# Fastino_Supply_Switching.net
KiCad netlist of a schematic drawn in Altium Designer
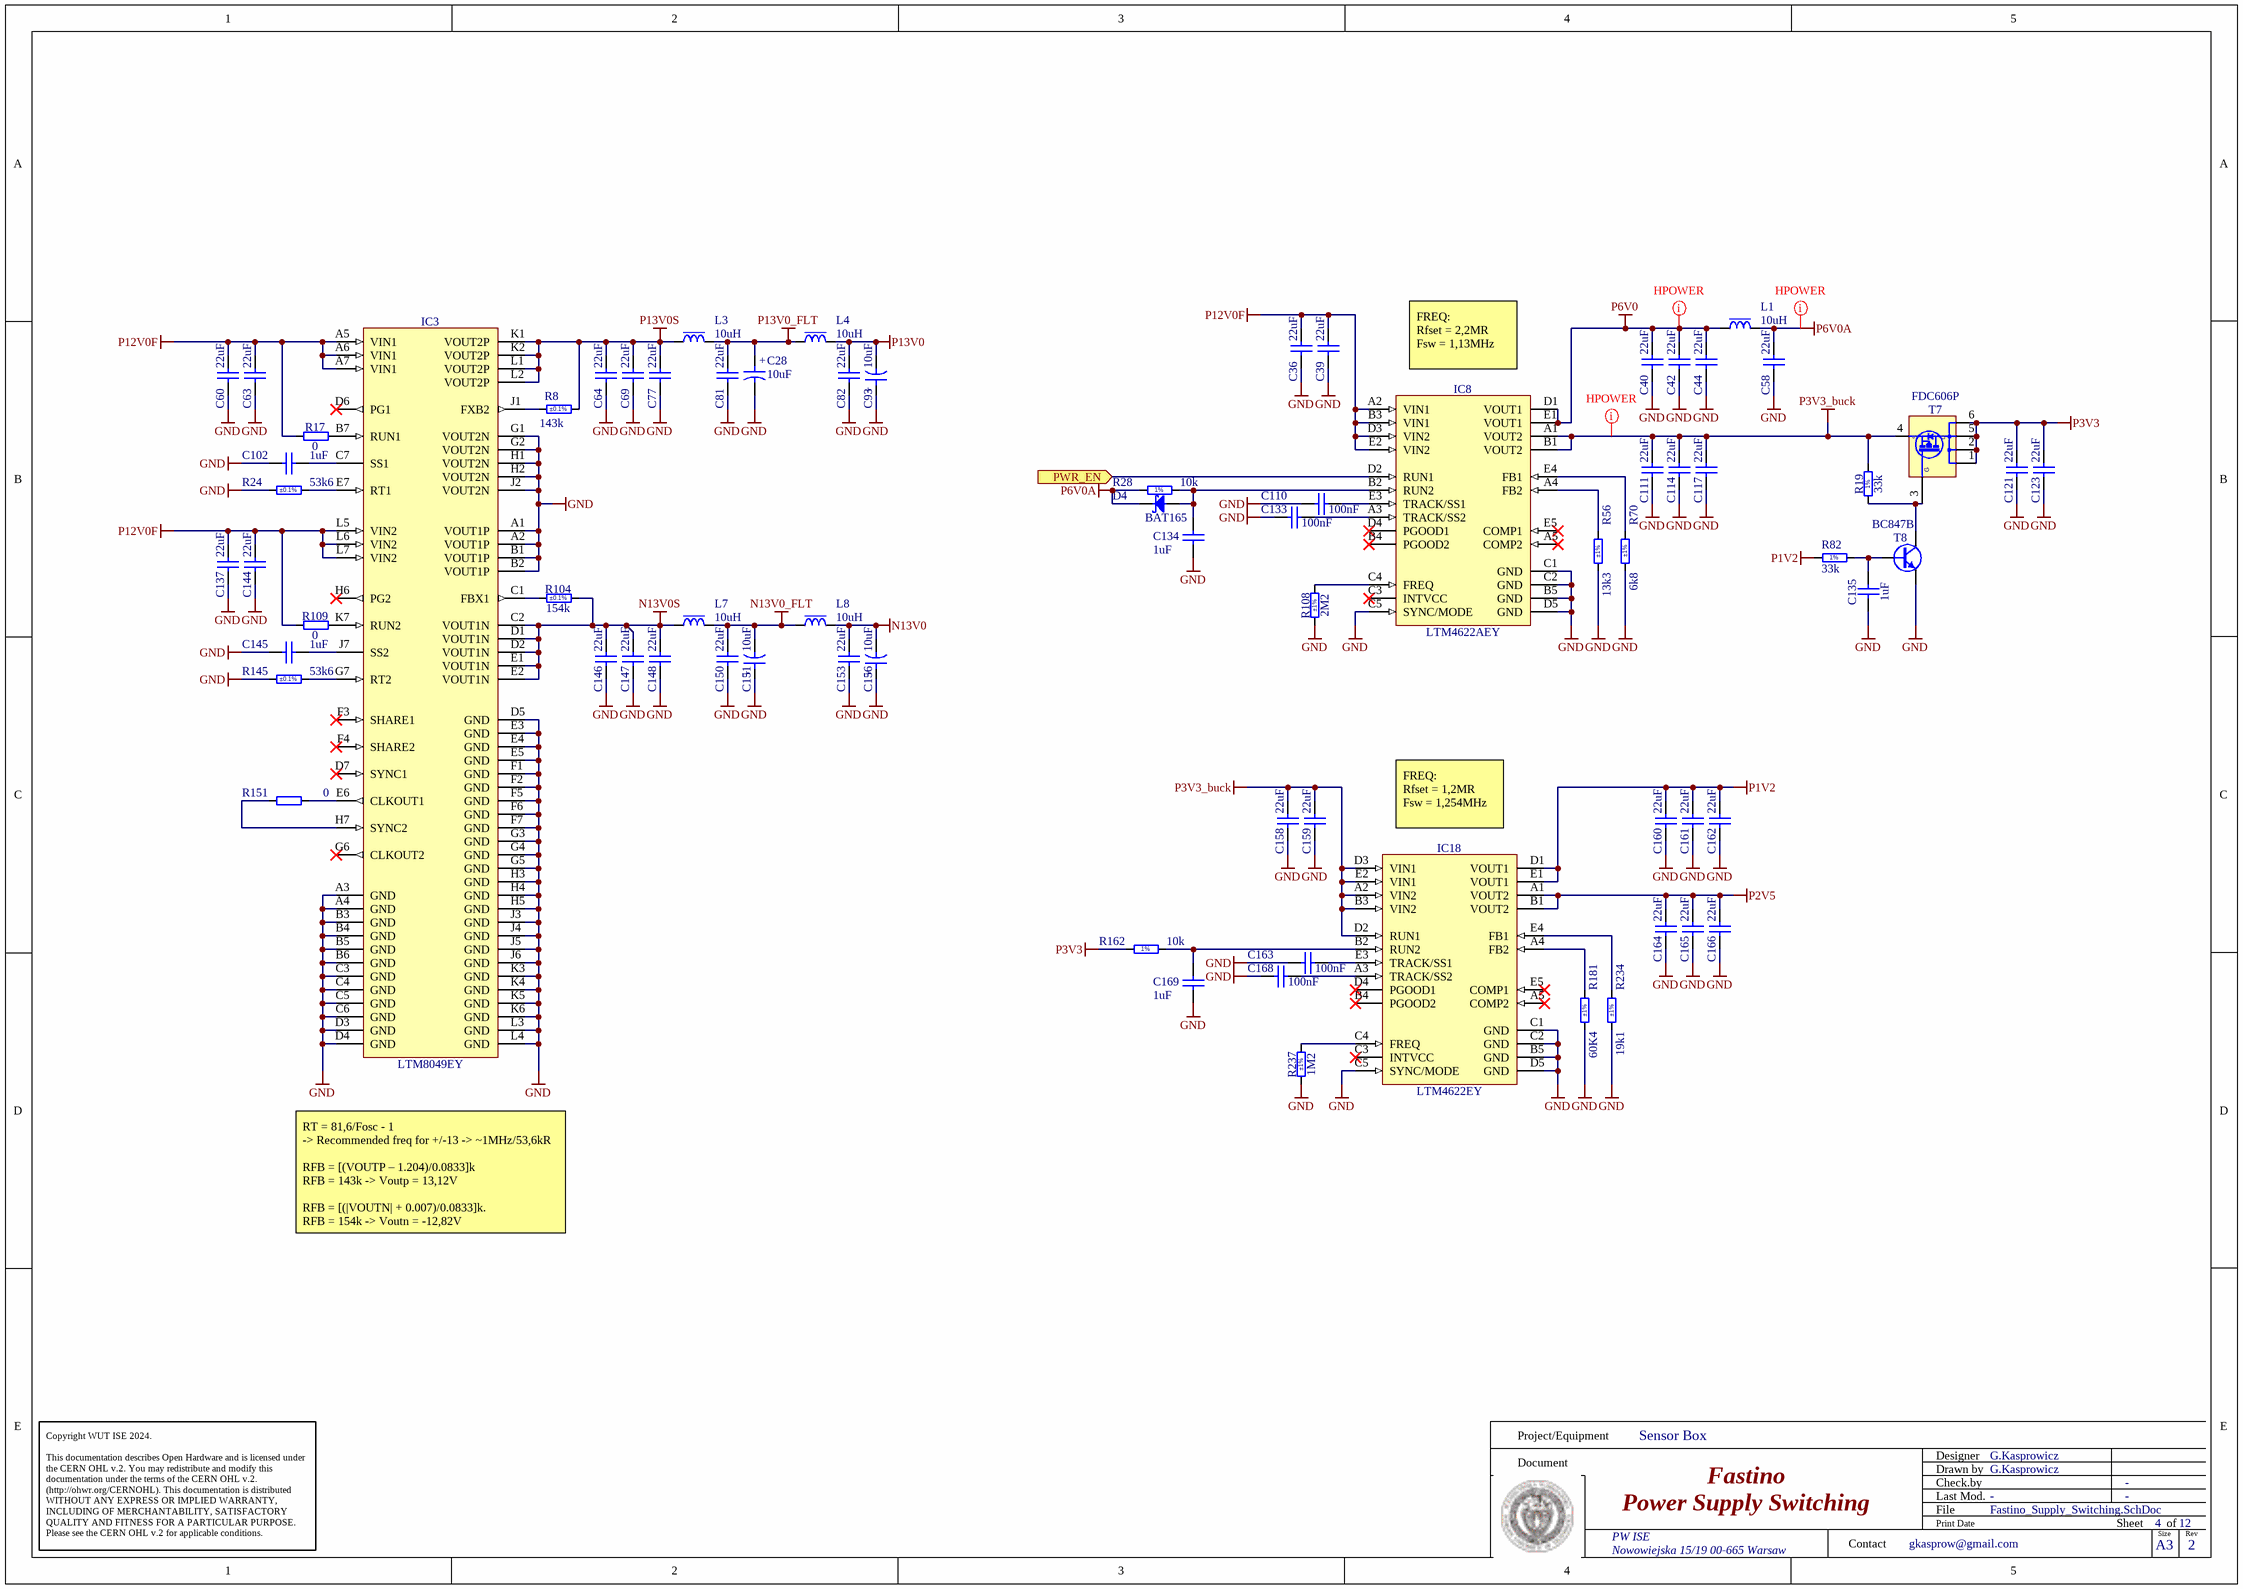
[diagram p0: Fastino_Supply_Switching.SchDoc]

(export (version "E")
  (design (tool "Eeschema 10.0.6"))
  (components
    (comp (ref "C28")
      (value "10uF")
      (footprint "CAPMP3216X180N")
      (description "Polarised capacitor")
      (fields
        (field (name "PART NUMBER") "CTE3216-18_10UF_16V_20%_AVX_TCJ")
        (field (name "VOLTAGE") "16V")
        (field (name "AUTHOR") "CERN DEM JLC")
      )
      (libsource (lib "Capacitors") (part "Capacitor - polarized"))
    )
    (comp (ref "C36")
      (value "22uF")
      (footprint "CAPC2012X135N")
      (description "Non-polarised capacitor")
      (fields
        (field (name "PART NUMBER") "CC0805_22UF_16V_10%_X5R")
        (field (name "VOLTAGE") "16V")
        (field (name "AUTHOR") "CERN DEM JLC")
      )
      (libsource (lib "Capacitors") (part "Capacitor - non polarized"))
    )
    (comp (ref "C39")
      (value "22uF")
      (footprint "CAPC2012X135N")
      (description "Non-polarised capacitor")
      (fields
        (field (name "PART NUMBER") "CC0805_22UF_16V_10%_X5R")
        (field (name "VOLTAGE") "16V")
        (field (name "AUTHOR") "CERN DEM JLC")
      )
      (libsource (lib "Capacitors") (part "Capacitor - non polarized"))
    )
    (comp (ref "C40")
      (value "22uF")
      (footprint "CAPC2012X135N")
      (description "Non-polarised capacitor")
      (fields
        (field (name "PART NUMBER") "CC0805_22UF_16V_10%_X5R")
        (field (name "VOLTAGE") "16V")
        (field (name "AUTHOR") "CERN DEM JLC")
      )
      (libsource (lib "Capacitors") (part "Capacitor - non polarized"))
    )
    (comp (ref "C42")
      (value "22uF")
      (footprint "CAPC2012X135N")
      (description "Non-polarised capacitor")
      (fields
        (field (name "PART NUMBER") "CC0805_22UF_16V_10%_X5R")
        (field (name "VOLTAGE") "16V")
        (field (name "AUTHOR") "CERN DEM JLC")
      )
      (libsource (lib "Capacitors") (part "Capacitor - non polarized"))
    )
    (comp (ref "C44")
      (value "22uF")
      (footprint "CAPC2012X135N")
      (description "Non-polarised capacitor")
      (fields
        (field (name "PART NUMBER") "CC0805_22UF_16V_10%_X5R")
        (field (name "VOLTAGE") "16V")
        (field (name "AUTHOR") "CERN DEM JLC")
      )
      (libsource (lib "Capacitors") (part "Capacitor - non polarized"))
    )
    (comp (ref "C58")
      (value "22uF")
      (footprint "CAPC2012X135N")
      (description "Non-polarised capacitor")
      (fields
        (field (name "PART NUMBER") "CC0805_22UF_16V_10%_X5R")
        (field (name "VOLTAGE") "16V")
        (field (name "AUTHOR") "CERN DEM JLC")
      )
      (libsource (lib "Capacitors") (part "Capacitor - non polarized"))
    )
    (comp (ref "C60")
      (value "22uF")
      (footprint "CAPC2012X135N")
      (description "Non-polarised capacitor")
      (fields
        (field (name "PART NUMBER") "CC0805_22UF_16V_10%_X5R")
        (field (name "VOLTAGE") "16V")
        (field (name "AUTHOR") "CERN DEM JLC")
      )
      (libsource (lib "Capacitors") (part "Capacitor - non polarized"))
    )
    (comp (ref "C63")
      (value "22uF")
      (footprint "CAPC2012X135N")
      (description "Non-polarised capacitor")
      (fields
        (field (name "PART NUMBER") "CC0805_22UF_16V_10%_X5R")
        (field (name "VOLTAGE") "16V")
        (field (name "AUTHOR") "CERN DEM JLC")
      )
      (libsource (lib "Capacitors") (part "Capacitor - non polarized"))
    )
    (comp (ref "C64")
      (value "22uF")
      (footprint "CAPC2012X135N")
      (description "Non-polarised capacitor")
      (fields
        (field (name "PART NUMBER") "CC0805_22UF_16V_10%_X5R")
        (field (name "VOLTAGE") "16V")
        (field (name "AUTHOR") "CERN DEM JLC")
      )
      (libsource (lib "Capacitors") (part "Capacitor - non polarized"))
    )
    (comp (ref "C69")
      (value "22uF")
      (footprint "CAPC2012X135N")
      (description "Non-polarised capacitor")
      (fields
        (field (name "PART NUMBER") "CC0805_22UF_16V_10%_X5R")
        (field (name "VOLTAGE") "16V")
        (field (name "AUTHOR") "CERN DEM JLC")
      )
      (libsource (lib "Capacitors") (part "Capacitor - non polarized"))
    )
    (comp (ref "C77")
      (value "22uF")
      (footprint "CAPC2012X135N")
      (description "Non-polarised capacitor")
      (fields
        (field (name "PART NUMBER") "CC0805_22UF_16V_10%_X5R")
        (field (name "VOLTAGE") "16V")
        (field (name "AUTHOR") "CERN DEM JLC")
      )
      (libsource (lib "Capacitors") (part "Capacitor - non polarized"))
    )
    (comp (ref "C81")
      (value "22uF")
      (footprint "CAPC2012X135N")
      (description "Non-polarised capacitor")
      (fields
        (field (name "PART NUMBER") "CC0805_22UF_16V_10%_X5R")
        (field (name "VOLTAGE") "16V")
        (field (name "AUTHOR") "CERN DEM JLC")
      )
      (libsource (lib "Capacitors") (part "Capacitor - non polarized"))
    )
    (comp (ref "C82")
      (value "22uF")
      (footprint "CAPC2012X135N")
      (description "Non-polarised capacitor")
      (fields
        (field (name "PART NUMBER") "CC0805_22UF_16V_10%_X5R")
        (field (name "VOLTAGE") "16V")
        (field (name "AUTHOR") "CERN DEM JLC")
      )
      (libsource (lib "Capacitors") (part "Capacitor - non polarized"))
    )
    (comp (ref "C93")
      (value "10uF")
      (footprint "CAPMP3216X180N")
      (description "Polarised capacitor")
      (fields
        (field (name "PART NUMBER") "CTE3216-18_10UF_16V_20%_AVX_TCJ")
        (field (name "VOLTAGE") "16V")
        (field (name "AUTHOR") "CERN DEM JLC")
      )
      (libsource (lib "Capacitors") (part "Capacitor - polarized"))
    )
    (comp (ref "C102")
      (value "1uF")
      (footprint "CAPC1608X87N")
      (description "Non-polarised capacitor")
      (fields
        (field (name "PART NUMBER") "CC0603_1UF_25V_10%_X7R")
        (field (name "VOLTAGE") "25V")
        (field (name "AUTHOR") "CERN DEM JLC")
      )
      (libsource (lib "Capacitors") (part "Capacitor - non polarized"))
    )
    (comp (ref "C110")
      (value "100nF")
      (footprint "CAPC1005X55N")
      (description "Non-polarised capacitor")
      (fields
        (field (name "PART NUMBER") "CC0402_100NF_16V_10%_X5R")
        (field (name "VOLTAGE") "16V")
        (field (name "AUTHOR") "CERN DEM JLC")
      )
      (libsource (lib "Capacitors") (part "Capacitor - non polarized"))
    )
    (comp (ref "C111")
      (value "22uF")
      (footprint "CAPC2012X135N")
      (description "Non-polarised capacitor")
      (fields
        (field (name "PART NUMBER") "CC0805_22UF_16V_10%_X5R")
        (field (name "VOLTAGE") "16V")
        (field (name "AUTHOR") "CERN DEM JLC")
      )
      (libsource (lib "Capacitors") (part "Capacitor - non polarized"))
    )
    (comp (ref "C114")
      (value "22uF")
      (footprint "CAPC2012X135N")
      (description "Non-polarised capacitor")
      (fields
        (field (name "PART NUMBER") "CC0805_22UF_16V_10%_X5R")
        (field (name "VOLTAGE") "16V")
        (field (name "AUTHOR") "CERN DEM JLC")
      )
      (libsource (lib "Capacitors") (part "Capacitor - non polarized"))
    )
    (comp (ref "C117")
      (value "22uF")
      (footprint "CAPC2012X135N")
      (description "Non-polarised capacitor")
      (fields
        (field (name "PART NUMBER") "CC0805_22UF_16V_10%_X5R")
        (field (name "VOLTAGE") "16V")
        (field (name "AUTHOR") "CERN DEM JLC")
      )
      (libsource (lib "Capacitors") (part "Capacitor - non polarized"))
    )
    (comp (ref "C121")
      (value "22uF")
      (footprint "CAPC2012X135N")
      (description "Non-polarised capacitor")
      (fields
        (field (name "PART NUMBER") "CC0805_22UF_16V_10%_X5R")
        (field (name "VOLTAGE") "16V")
        (field (name "AUTHOR") "CERN DEM JLC")
      )
      (libsource (lib "Capacitors") (part "Capacitor - non polarized"))
    )
    (comp (ref "C123")
      (value "22uF")
      (footprint "CAPC2012X135N")
      (description "Non-polarised capacitor")
      (fields
        (field (name "PART NUMBER") "CC0805_22UF_16V_10%_X5R")
        (field (name "VOLTAGE") "16V")
        (field (name "AUTHOR") "CERN DEM JLC")
      )
      (libsource (lib "Capacitors") (part "Capacitor - non polarized"))
    )
    (comp (ref "C133")
      (value "100nF")
      (footprint "CAPC1005X55N")
      (description "Non-polarised capacitor")
      (fields
        (field (name "PART NUMBER") "CC0402_100NF_16V_10%_X5R")
        (field (name "VOLTAGE") "16V")
        (field (name "AUTHOR") "CERN DEM JLC")
      )
      (libsource (lib "Capacitors") (part "Capacitor - non polarized"))
    )
    (comp (ref "C134")
      (value "1uF")
      (footprint "CAPC1608X87N")
      (description "Non-polarised capacitor")
      (fields
        (field (name "PART NUMBER") "CC0603_1UF_25V_10%_X7R")
        (field (name "VOLTAGE") "25V")
        (field (name "AUTHOR") "CERN DEM JLC")
      )
      (libsource (lib "Capacitors") (part "Capacitor - non polarized"))
    )
    (comp (ref "C135")
      (value "1uF")
      (footprint "CAPC1608X87N")
      (description "Non-polarised capacitor")
      (fields
        (field (name "PART NUMBER") "CC0603_1UF_25V_10%_X7R")
        (field (name "VOLTAGE") "25V")
        (field (name "AUTHOR") "CERN DEM JLC")
      )
      (libsource (lib "Capacitors") (part "Capacitor - non polarized"))
    )
    (comp (ref "C137")
      (value "22uF")
      (footprint "CAPC2012X135N")
      (description "Non-polarised capacitor")
      (fields
        (field (name "PART NUMBER") "CC0805_22UF_16V_10%_X5R")
        (field (name "VOLTAGE") "16V")
        (field (name "AUTHOR") "CERN DEM JLC")
      )
      (libsource (lib "Capacitors") (part "Capacitor - non polarized"))
    )
    (comp (ref "C144")
      (value "22uF")
      (footprint "CAPC2012X135N")
      (description "Non-polarised capacitor")
      (fields
        (field (name "PART NUMBER") "CC0805_22UF_16V_10%_X5R")
        (field (name "VOLTAGE") "16V")
        (field (name "AUTHOR") "CERN DEM JLC")
      )
      (libsource (lib "Capacitors") (part "Capacitor - non polarized"))
    )
    (comp (ref "C145")
      (value "1uF")
      (footprint "CAPC1608X87N")
      (description "Non-polarised capacitor")
      (fields
        (field (name "PART NUMBER") "CC0603_1UF_25V_10%_X7R")
        (field (name "VOLTAGE") "25V")
        (field (name "AUTHOR") "CERN DEM JLC")
      )
      (libsource (lib "Capacitors") (part "Capacitor - non polarized"))
    )
    (comp (ref "C146")
      (value "22uF")
      (footprint "CAPC2012X135N")
      (description "Non-polarised capacitor")
      (fields
        (field (name "PART NUMBER") "CC0805_22UF_16V_10%_X5R")
        (field (name "VOLTAGE") "16V")
        (field (name "AUTHOR") "CERN DEM JLC")
      )
      (libsource (lib "Capacitors") (part "Capacitor - non polarized"))
    )
    (comp (ref "C147")
      (value "22uF")
      (footprint "CAPC2012X135N")
      (description "Non-polarised capacitor")
      (fields
        (field (name "PART NUMBER") "CC0805_22UF_16V_10%_X5R")
        (field (name "VOLTAGE") "16V")
        (field (name "AUTHOR") "CERN DEM JLC")
      )
      (libsource (lib "Capacitors") (part "Capacitor - non polarized"))
    )
    (comp (ref "C148")
      (value "22uF")
      (footprint "CAPC2012X135N")
      (description "Non-polarised capacitor")
      (fields
        (field (name "PART NUMBER") "CC0805_22UF_16V_10%_X5R")
        (field (name "VOLTAGE") "16V")
        (field (name "AUTHOR") "CERN DEM JLC")
      )
      (libsource (lib "Capacitors") (part "Capacitor - non polarized"))
    )
    (comp (ref "C150")
      (value "22uF")
      (footprint "CAPC2012X135N")
      (description "Non-polarised capacitor")
      (fields
        (field (name "PART NUMBER") "CC0805_22UF_16V_10%_X5R")
        (field (name "VOLTAGE") "16V")
        (field (name "AUTHOR") "CERN DEM JLC")
      )
      (libsource (lib "Capacitors") (part "Capacitor - non polarized"))
    )
    (comp (ref "C151")
      (value "10uF")
      (footprint "CAPMP3216X180N")
      (description "Polarised capacitor")
      (fields
        (field (name "PART NUMBER") "CTE3216-18_10UF_16V_20%_AVX_TCJ")
        (field (name "VOLTAGE") "16V")
        (field (name "AUTHOR") "CERN DEM JLC")
      )
      (libsource (lib "Capacitors") (part "Capacitor - polarized"))
    )
    (comp (ref "C153")
      (value "22uF")
      (footprint "CAPC2012X135N")
      (description "Non-polarised capacitor")
      (fields
        (field (name "PART NUMBER") "CC0805_22UF_16V_10%_X5R")
        (field (name "VOLTAGE") "16V")
        (field (name "AUTHOR") "CERN DEM JLC")
      )
      (libsource (lib "Capacitors") (part "Capacitor - non polarized"))
    )
    (comp (ref "C156")
      (value "10uF")
      (footprint "CAPMP3216X180N")
      (description "Polarised capacitor")
      (fields
        (field (name "PART NUMBER") "CTE3216-18_10UF_16V_20%_AVX_TCJ")
        (field (name "VOLTAGE") "16V")
        (field (name "AUTHOR") "CERN DEM JLC")
      )
      (libsource (lib "Capacitors") (part "Capacitor - polarized"))
    )
    (comp (ref "C158")
      (value "22uF")
      (footprint "CAPC2012X135N")
      (description "Non-polarised capacitor")
      (fields
        (field (name "PART NUMBER") "CC0805_22UF_16V_10%_X5R")
        (field (name "VOLTAGE") "16V")
        (field (name "AUTHOR") "CERN DEM JLC")
      )
      (libsource (lib "Capacitors") (part "Capacitor - non polarized"))
    )
    (comp (ref "C159")
      (value "22uF")
      (footprint "CAPC2012X135N")
      (description "Non-polarised capacitor")
      (fields
        (field (name "PART NUMBER") "CC0805_22UF_16V_10%_X5R")
        (field (name "VOLTAGE") "16V")
        (field (name "AUTHOR") "CERN DEM JLC")
      )
      (libsource (lib "Capacitors") (part "Capacitor - non polarized"))
    )
    (comp (ref "C160")
      (value "22uF")
      (footprint "CAPC2012X135N")
      (description "Non-polarised capacitor")
      (fields
        (field (name "PART NUMBER") "CC0805_22UF_16V_10%_X5R")
        (field (name "VOLTAGE") "16V")
        (field (name "AUTHOR") "CERN DEM JLC")
      )
      (libsource (lib "Capacitors") (part "Capacitor - non polarized"))
    )
    (comp (ref "C161")
      (value "22uF")
      (footprint "CAPC2012X135N")
      (description "Non-polarised capacitor")
      (fields
        (field (name "PART NUMBER") "CC0805_22UF_16V_10%_X5R")
        (field (name "VOLTAGE") "16V")
        (field (name "AUTHOR") "CERN DEM JLC")
      )
      (libsource (lib "Capacitors") (part "Capacitor - non polarized"))
    )
    (comp (ref "C162")
      (value "22uF")
      (footprint "CAPC2012X135N")
      (description "Non-polarised capacitor")
      (fields
        (field (name "PART NUMBER") "CC0805_22UF_16V_10%_X5R")
        (field (name "VOLTAGE") "16V")
        (field (name "AUTHOR") "CERN DEM JLC")
      )
      (libsource (lib "Capacitors") (part "Capacitor - non polarized"))
    )
    (comp (ref "C163")
      (value "100nF")
      (footprint "CAPC1005X55N")
      (description "Non-polarised capacitor")
      (fields
        (field (name "PART NUMBER") "CC0402_100NF_16V_10%_X5R")
        (field (name "VOLTAGE") "16V")
        (field (name "AUTHOR") "CERN DEM JLC")
      )
      (libsource (lib "Capacitors") (part "Capacitor - non polarized"))
    )
    (comp (ref "C164")
      (value "22uF")
      (footprint "CAPC2012X135N")
      (description "Non-polarised capacitor")
      (fields
        (field (name "PART NUMBER") "CC0805_22UF_16V_10%_X5R")
        (field (name "VOLTAGE") "16V")
        (field (name "AUTHOR") "CERN DEM JLC")
      )
      (libsource (lib "Capacitors") (part "Capacitor - non polarized"))
    )
    (comp (ref "C165")
      (value "22uF")
      (footprint "CAPC2012X135N")
      (description "Non-polarised capacitor")
      (fields
        (field (name "PART NUMBER") "CC0805_22UF_16V_10%_X5R")
        (field (name "VOLTAGE") "16V")
        (field (name "AUTHOR") "CERN DEM JLC")
      )
      (libsource (lib "Capacitors") (part "Capacitor - non polarized"))
    )
    (comp (ref "C166")
      (value "22uF")
      (footprint "CAPC2012X135N")
      (description "Non-polarised capacitor")
      (fields
        (field (name "PART NUMBER") "CC0805_22UF_16V_10%_X5R")
        (field (name "VOLTAGE") "16V")
        (field (name "AUTHOR") "CERN DEM JLC")
      )
      (libsource (lib "Capacitors") (part "Capacitor - non polarized"))
    )
    (comp (ref "C168")
      (value "100nF")
      (footprint "CAPC1005X55N")
      (description "Non-polarised capacitor")
      (fields
        (field (name "PART NUMBER") "CC0402_100NF_16V_10%_X5R")
        (field (name "VOLTAGE") "16V")
        (field (name "AUTHOR") "CERN DEM JLC")
      )
      (libsource (lib "Capacitors") (part "Capacitor - non polarized"))
    )
    (comp (ref "C169")
      (value "1uF")
      (footprint "CAPC1608X87N")
      (description "Non-polarised capacitor")
      (fields
        (field (name "PART NUMBER") "CC0603_1UF_25V_10%_X7R")
        (field (name "VOLTAGE") "25V")
        (field (name "AUTHOR") "CERN DEM JLC")
      )
      (libsource (lib "Capacitors") (part "Capacitor - non polarized"))
    )
    (comp (ref "D4")
      (value "BAT165")
      (footprint "SOD2512X110N")
      (description "Schottky Diode")
      (fields
        (field (name "MANUFACTURER") "INFINEON")
        (field (name "VOLTAGE") "40V")
        (field (name "AUTHOR") "CERN DEM JLC")
      )
      (libsource (lib "ICs And Semiconductors") (part "Diode Schottky"))
    )
    (comp (ref "IC3")
      (value "LTM8049EY")
      (footprint "BGA77C127P7X11_900X1500X262")
      (description "Dual SEPIC or Inverting uModule DC/DC Converter")
      (fields
        (field (name "PART NUMBER") "LTM8049EY#PBF")
        (field (name "MANUFACTURER") "LINEAR TECHNOLOGY")
        (field (name "AUTHOR") "CERN DEM JLC")
      )
      (libsource (lib "ICs And Semiconductors") (part "LTM8049"))
    )
    (comp (ref "IC8")
      (value "LTM4622AEY")
      (footprint "BGA25C127P5X5_625X625X262")
      (description "3.6V-20V To 1.5V-12V, Dual 2A or Single 4A  Ultrathin Step-Down DC/DC µModule Regulator")
      (fields
        (field (name "PART NUMBER") "LTM4622AEY#PBF")
        (field (name "MANUFACTURER") "LINEAR TECHNOLOGY")
        (field (name "AUTHOR") "CERN DEM MR")
      )
      (libsource (lib "ICs And Semiconductors") (part "LTM4622A"))
    )
    (comp (ref "IC18")
      (value "LTM4622EY")
      (footprint "BGA25C127P5X5_625X625X262")
      (description "3.6V-20V To 1.5V-12V, Dual 2A or Single 5A  Ultrathin Step-Down DC/DC µModule Regulator")
      (fields (field (name "MANUFACTURER") "ANALOG DEVICES") (field (name "AUTHOR") "CERN DEM HF"))
      (libsource (lib "ICs And Semiconductors") (part "LTM4622"))
    )
    (comp (ref "L1")
      (value "10uH")
      (footprint "IND_MURATA-PS_8400")
      (description "Inductor With Core")
      (fields
        (field (name "PART NUMBER") "IND_10UH_10%_MURATA-PS_8400")
        (field (name "POWER") "950mA")
        (field (name "AUTHOR") "CERN DEM JLC")
      )
      (libsource (lib "Inductors & Transformers") (part "Inductor With Magnetic core"))
    )
    (comp (ref "L3")
      (value "10uH")
      (footprint "IND_MURATA-PS_8400")
      (description "Inductor With Core")
      (fields
        (field (name "PART NUMBER") "IND_10UH_10%_MURATA-PS_8400")
        (field (name "POWER") "950mA")
        (field (name "AUTHOR") "CERN DEM JLC")
      )
      (libsource (lib "Inductors & Transformers") (part "Inductor With Magnetic core"))
    )
    (comp (ref "L4")
      (value "10uH")
      (footprint "IND_MURATA-PS_8400")
      (description "Inductor With Core")
      (fields
        (field (name "PART NUMBER") "IND_10UH_10%_MURATA-PS_8400")
        (field (name "POWER") "950mA")
        (field (name "AUTHOR") "CERN DEM JLC")
      )
      (libsource (lib "Inductors & Transformers") (part "Inductor With Magnetic core"))
    )
    (comp (ref "L7")
      (value "10uH")
      (footprint "IND_MURATA-PS_8400")
      (description "Inductor With Core")
      (fields
        (field (name "PART NUMBER") "IND_10UH_10%_MURATA-PS_8400")
        (field (name "POWER") "950mA")
        (field (name "AUTHOR") "CERN DEM JLC")
      )
      (libsource (lib "Inductors & Transformers") (part "Inductor With Magnetic core"))
    )
    (comp (ref "L8")
      (value "10uH")
      (footprint "IND_MURATA-PS_8400")
      (description "Inductor With Core")
      (fields
        (field (name "PART NUMBER") "IND_10UH_10%_MURATA-PS_8400")
        (field (name "POWER") "950mA")
        (field (name "AUTHOR") "CERN DEM JLC")
      )
      (libsource (lib "Inductors & Transformers") (part "Inductor With Magnetic core"))
    )
    (comp (ref "R8")
      (value "143k")
      (footprint "RESC1608X55N")
      (description "Resistor - 0.1%")
      (fields
        (field (name "TOLERANCE") "±0.1%")
        (field (name "PART NUMBER") "R0603_143K_0.1%_0.063W_10PPM")
        (field (name "POWER") "0.063W")
        (field (name "AUTHOR") "CERN DEM JLC")
      )
      (libsource (lib "Resistors") (part "Resistor - 0.1%"))
    )
    (comp (ref "R17")
      (value "0")
      (footprint "RESC1005X40N")
      (description "Resistor")
      (fields
        (field (name "PART NUMBER") "R0402_0R_JUMPER")
        (field (name "MANUFACTURER") "GENERIC")
        (field (name "AUTHOR") "CERN DEM JLC")
      )
      (libsource (lib "Resistors") (part "Resistor"))
    )
    (comp (ref "R19")
      (value "33k")
      (footprint "RESC1005X40N")
      (description "Resistor - 1%")
      (fields
        (field (name "PART NUMBER") "R0402_33K_1%_0.0625W_100PPM")
        (field (name "POWER") "0.0625W")
        (field (name "AUTHOR") "CERN DEM JLC")
      )
      (libsource (lib "Resistors") (part "Resistor - 1%"))
    )
    (comp (ref "R24")
      (value "53k6")
      (footprint "RESC1608X55N")
      (description "Resistor - 0.1%")
      (fields
        (field (name "TOLERANCE") "±0.1%")
        (field (name "PART NUMBER") "R0603_53K6_0.1%_0.063W_10PPM")
        (field (name "POWER") "0.063W")
        (field (name "AUTHOR") "CERN DEM JLC")
      )
      (libsource (lib "Resistors") (part "Resistor - 0.1%"))
    )
    (comp (ref "R28")
      (value "10k")
      (footprint "RESC1005X40N")
      (description "Resistor - 1%")
      (fields
        (field (name "PART NUMBER") "R0402_10K_1%_0.0625W_100PPM")
        (field (name "POWER") "0.0625W")
        (field (name "AUTHOR") "CERN DEM JLC")
      )
      (libsource (lib "Resistors") (part "Resistor - 1%"))
    )
    (comp (ref "R56")
      (value "13k3")
      (footprint "RESC1005X40N")
      (description "Resistor - 1%")
      (fields
        (field (name "TOLERANCE") "±1%")
        (field (name "PART NUMBER") "R0402_13K3_1%_0.0625W_100PPM")
        (field (name "POWER") "0.0625W")
        (field (name "AUTHOR") "CERN DEM BC")
      )
      (libsource (lib "Resistors") (part "Resistor - 1%"))
    )
    (comp (ref "R70")
      (value "6k8")
      (footprint "RESC1005X40N")
      (description "Resistor - 1%")
      (fields
        (field (name "TOLERANCE") "±1%")
        (field (name "PART NUMBER") "R0402_6K8_1%_0.0625W_100PPM")
        (field (name "POWER") "0.0625W")
        (field (name "AUTHOR") "CERN DEM JLC")
      )
      (libsource (lib "Resistors") (part "Resistor - 1%"))
    )
    (comp (ref "R82")
      (value "33k")
      (footprint "RESC1005X40N")
      (description "Resistor - 1%")
      (fields
        (field (name "PART NUMBER") "R0402_33K_1%_0.0625W_100PPM")
        (field (name "POWER") "0.0625W")
        (field (name "AUTHOR") "CERN DEM JLC")
      )
      (libsource (lib "Resistors") (part "Resistor - 1%"))
    )
    (comp (ref "R104")
      (value "154k")
      (footprint "RESC2012X60N")
      (description "Resistor - 0.1%")
      (fields
        (field (name "TOLERANCE") "±0.1%")
        (field (name "PART NUMBER") "R0805_154K_0.1%_0.1W_25PPM")
        (field (name "POWER") "0.1W")
        (field (name "AUTHOR") "CERN DEM JLC")
      )
      (libsource (lib "Resistors") (part "Resistor - 0.1%"))
    )
    (comp (ref "R108")
      (value "2M2")
      (footprint "RESC1005X40N")
      (description "Resistor - 1%")
      (fields
        (field (name "TOLERANCE") "±1%")
        (field (name "PART NUMBER") "R0402_2M2_1%_0.0625W_100PPM")
        (field (name "POWER") "0.0625W")
        (field (name "AUTHOR") "CERN DEM JLC")
      )
      (libsource (lib "Resistors") (part "Resistor - 1%"))
    )
    (comp (ref "R109")
      (value "0")
      (footprint "RESC1005X40N")
      (description "Resistor")
      (fields
        (field (name "PART NUMBER") "R0402_0R_JUMPER")
        (field (name "MANUFACTURER") "GENERIC")
        (field (name "AUTHOR") "CERN DEM JLC")
      )
      (libsource (lib "Resistors") (part "Resistor"))
    )
    (comp (ref "R145")
      (value "53k6")
      (footprint "RESC1608X55N")
      (description "Resistor - 0.1%")
      (fields
        (field (name "TOLERANCE") "±0.1%")
        (field (name "PART NUMBER") "R0603_53K6_0.1%_0.063W_10PPM")
        (field (name "POWER") "0.063W")
        (field (name "AUTHOR") "CERN DEM JLC")
      )
      (libsource (lib "Resistors") (part "Resistor - 0.1%"))
    )
    (comp (ref "R151")
      (value "0")
      (footprint "RESC1005X40N")
      (description "Resistor")
      (fields
        (field (name "PART NUMBER") "R0402_0R_JUMPER")
        (field (name "MANUFACTURER") "GENERIC")
        (field (name "AUTHOR") "CERN DEM JLC")
      )
      (libsource (lib "Resistors") (part "Resistor"))
    )
    (comp (ref "R162")
      (value "10k")
      (footprint "RESC1005X40N")
      (description "Resistor - 1%")
      (fields
        (field (name "PART NUMBER") "R0402_10K_1%_0.0625W_100PPM")
        (field (name "POWER") "0.0625W")
        (field (name "AUTHOR") "CERN DEM JLC")
      )
      (libsource (lib "Resistors") (part "Resistor - 1%"))
    )
    (comp (ref "R181")
      (value "60K4")
      (footprint "RESC1005X40N")
      (description "Resistor - 1%")
      (fields
        (field (name "TOLERANCE") "±1%")
        (field (name "PART NUMBER") "R0402_60K4_1%_0.063W_100PPM")
        (field (name "POWER") "0.063W")
        (field (name "AUTHOR") "CERN DEM BC")
      )
      (libsource (lib "Resistors") (part "Resistor - 1%"))
    )
    (comp (ref "R234")
      (value "19k1")
      (footprint "RESC1608X55N")
      (description "Resistor - 1%")
      (fields
        (field (name "TOLERANCE") "±1%")
        (field (name "PART NUMBER") "R0603_19k1_1%_0.1W_100PPM")
        (field (name "POWER") "0.1W")
        (field (name "AUTHOR") "CERN DEM JLC")
      )
      (libsource (lib "") (part "Resistor - 1%_1"))
    )
    (comp (ref "R237")
      (value "1M2")
      (footprint "RESC1005X40N")
      (description "Resistor - 1%")
      (fields
        (field (name "TOLERANCE") "±1%")
        (field (name "PART NUMBER") "R0402_1M2_1%_0.0625W_100PPM")
        (field (name "POWER") "0.0625W")
        (field (name "AUTHOR") "CERN DEM JLC")
      )
      (libsource (lib "Resistors") (part "Resistor - 1%"))
    )
    (comp (ref "T7")
      (value "FDC606P")
      (footprint "SOT95P275X110-6N")
      (description "P-Channel 1.8V Specified PowerTrench MOSFET")
      (fields (field (name "MANUFACTURER") "ON SEMICONDUCTOR") (field (name "AUTHOR") "CERN DEM HF"))
      (libsource (lib "ICs And Semiconductors") (part "FDC606P"))
    )
    (comp (ref "T8")
      (value "BC847B")
      (footprint "SOT95P230X110-3N")
      (description "NPN Transistor")
      (fields (field (name "MANUFACTURER") "NXP SEMICONDUCTORS") (field (name "AUTHOR") "CERN DEM JLC"))
      (libsource (lib "ICs And Semiconductors") (part "NPN B1 E2 C3"))
    )
  )
  (nets
    (net (code "1") (name "/PWR_EN") (class "Default")
      (node (ref "IC8") (pin "D2") (pinfunction "RUN1_D2") (pintype "input"))
    )
    (net (code "2") (name "GND") (class "Default")
      (node (ref "C102") (pin "2") (pinfunction "2_2") (pintype "passive"))
      (node (ref "C110") (pin "2") (pinfunction "2_2") (pintype "passive"))
      (node (ref "C111") (pin "1") (pinfunction "1_1") (pintype "passive"))
      (node (ref "C114") (pin "1") (pinfunction "1_1") (pintype "passive"))
      (node (ref "C117") (pin "1") (pinfunction "1_1") (pintype "passive"))
      (node (ref "C121") (pin "1") (pinfunction "1_1") (pintype "passive"))
      (node (ref "C123") (pin "1") (pinfunction "1_1") (pintype "passive"))
      (node (ref "C133") (pin "2") (pinfunction "2_2") (pintype "passive"))
      (node (ref "C134") (pin "1") (pinfunction "1_1") (pintype "passive"))
      (node (ref "C135") (pin "1") (pinfunction "1_1") (pintype "passive"))
      (node (ref "C137") (pin "1") (pinfunction "1_1") (pintype "passive"))
      (node (ref "C144") (pin "1") (pinfunction "1_1") (pintype "passive"))
      (node (ref "C145") (pin "2") (pinfunction "2_2") (pintype "passive"))
      (node (ref "C146") (pin "1") (pinfunction "1_1") (pintype "passive"))
      (node (ref "C147") (pin "1") (pinfunction "1_1") (pintype "passive"))
      (node (ref "C148") (pin "1") (pinfunction "1_1") (pintype "passive"))
      (node (ref "C150") (pin "1") (pinfunction "1_1") (pintype "passive"))
      (node (ref "C151") (pin "1") (pinfunction "1_1") (pintype "passive"))
      (node (ref "C153") (pin "1") (pinfunction "1_1") (pintype "passive"))
      (node (ref "C156") (pin "1") (pinfunction "1_1") (pintype "passive"))
      (node (ref "C158") (pin "1") (pinfunction "1_1") (pintype "passive"))
      (node (ref "C159") (pin "1") (pinfunction "1_1") (pintype "passive"))
      (node (ref "C160") (pin "1") (pinfunction "1_1") (pintype "passive"))
      (node (ref "C161") (pin "1") (pinfunction "1_1") (pintype "passive"))
      (node (ref "C162") (pin "1") (pinfunction "1_1") (pintype "passive"))
      (node (ref "C163") (pin "2") (pinfunction "2_2") (pintype "passive"))
      (node (ref "C164") (pin "1") (pinfunction "1_1") (pintype "passive"))
      (node (ref "C165") (pin "1") (pinfunction "1_1") (pintype "passive"))
      (node (ref "C166") (pin "1") (pinfunction "1_1") (pintype "passive"))
      (node (ref "C168") (pin "2") (pinfunction "2_2") (pintype "passive"))
      (node (ref "C169") (pin "1") (pinfunction "1_1") (pintype "passive"))
      (node (ref "C28") (pin "2") (pinfunction "2_2") (pintype "passive"))
      (node (ref "C36") (pin "1") (pinfunction "1_1") (pintype "passive"))
      (node (ref "C39") (pin "1") (pinfunction "1_1") (pintype "passive"))
      (node (ref "C40") (pin "1") (pinfunction "1_1") (pintype "passive"))
      (node (ref "C42") (pin "1") (pinfunction "1_1") (pintype "passive"))
      (node (ref "C44") (pin "1") (pinfunction "1_1") (pintype "passive"))
      (node (ref "C58") (pin "1") (pinfunction "1_1") (pintype "passive"))
      (node (ref "C60") (pin "1") (pinfunction "1_1") (pintype "passive"))
      (node (ref "C63") (pin "1") (pinfunction "1_1") (pintype "passive"))
      (node (ref "C64") (pin "1") (pinfunction "1_1") (pintype "passive"))
      (node (ref "C69") (pin "1") (pinfunction "1_1") (pintype "passive"))
      (node (ref "C77") (pin "1") (pinfunction "1_1") (pintype "passive"))
      (node (ref "C81") (pin "1") (pinfunction "1_1") (pintype "passive"))
      (node (ref "C82") (pin "1") (pinfunction "1_1") (pintype "passive"))
      (node (ref "C93") (pin "1") (pinfunction "1_1") (pintype "passive"))
      (node (ref "IC18") (pin "B5") (pinfunction "GND_B5") (pintype "power_in"))
      (node (ref "IC18") (pin "C1") (pinfunction "GND_C1") (pintype "power_in"))
      (node (ref "IC18") (pin "C2") (pinfunction "GND_C2") (pintype "power_in"))
      (node (ref "IC18") (pin "C5") (pinfunction "SYNC/MODE_C5") (pintype "input"))
      (node (ref "IC18") (pin "D5") (pinfunction "GND_D5") (pintype "power_in"))
      (node (ref "IC3") (pin "A1") (pinfunction "VOUT1P_A1") (pintype "power_in"))
      (node (ref "IC3") (pin "A2") (pinfunction "VOUT1P_A2") (pintype "power_in"))
      (node (ref "IC3") (pin "A3") (pinfunction "GND_A3") (pintype "power_in"))
      (node (ref "IC3") (pin "A4") (pinfunction "GND_A4") (pintype "power_in"))
      (node (ref "IC3") (pin "B1") (pinfunction "VOUT1P_B1") (pintype "power_in"))
      (node (ref "IC3") (pin "B2") (pinfunction "VOUT1P_B2") (pintype "power_in"))
      (node (ref "IC3") (pin "B3") (pinfunction "GND_B3") (pintype "power_in"))
      (node (ref "IC3") (pin "B4") (pinfunction "GND_B4") (pintype "power_in"))
      (node (ref "IC3") (pin "B5") (pinfunction "GND_B5") (pintype "power_in"))
      (node (ref "IC3") (pin "B6") (pinfunction "GND_B6") (pintype "power_in"))
      (node (ref "IC3") (pin "C3") (pinfunction "GND_C3") (pintype "power_in"))
      (node (ref "IC3") (pin "C4") (pinfunction "GND_C4") (pintype "power_in"))
      (node (ref "IC3") (pin "C5") (pinfunction "GND_C5") (pintype "power_in"))
      (node (ref "IC3") (pin "C6") (pinfunction "GND_C6") (pintype "power_in"))
      (node (ref "IC3") (pin "D3") (pinfunction "GND_D3") (pintype "power_in"))
      (node (ref "IC3") (pin "D4") (pinfunction "GND_D4") (pintype "power_in"))
      (node (ref "IC3") (pin "D5") (pinfunction "GND_D5") (pintype "power_in"))
      (node (ref "IC3") (pin "E3") (pinfunction "GND_E3") (pintype "power_in"))
      (node (ref "IC3") (pin "E4") (pinfunction "GND_E4") (pintype "power_in"))
      (node (ref "IC3") (pin "E5") (pinfunction "GND_E5") (pintype "power_in"))
      (node (ref "IC3") (pin "F1") (pinfunction "GND_F1") (pintype "power_in"))
      (node (ref "IC3") (pin "F2") (pinfunction "GND_F2") (pintype "power_in"))
      (node (ref "IC3") (pin "F5") (pinfunction "GND_F5") (pintype "power_in"))
      (node (ref "IC3") (pin "F6") (pinfunction "GND_F6") (pintype "power_in"))
      (node (ref "IC3") (pin "F7") (pinfunction "GND_F7") (pintype "power_in"))
      (node (ref "IC3") (pin "G1") (pinfunction "VOUT2N_G1") (pintype "power_in"))
      (node (ref "IC3") (pin "G2") (pinfunction "VOUT2N_G2") (pintype "power_in"))
      (node (ref "IC3") (pin "G3") (pinfunction "GND_G3") (pintype "power_in"))
      (node (ref "IC3") (pin "G4") (pinfunction "GND_G4") (pintype "power_in"))
      (node (ref "IC3") (pin "G5") (pinfunction "GND_G5") (pintype "power_in"))
      (node (ref "IC3") (pin "H1") (pinfunction "VOUT2N_H1") (pintype "power_in"))
      (node (ref "IC3") (pin "H2") (pinfunction "VOUT2N_H2") (pintype "power_in"))
      (node (ref "IC3") (pin "H3") (pinfunction "GND_H3") (pintype "power_in"))
      (node (ref "IC3") (pin "H4") (pinfunction "GND_H4") (pintype "power_in"))
      (node (ref "IC3") (pin "H5") (pinfunction "GND_H5") (pintype "power_in"))
      (node (ref "IC3") (pin "J2") (pinfunction "VOUT2N_J2") (pintype "power_in"))
      (node (ref "IC3") (pin "J3") (pinfunction "GND_J3") (pintype "power_in"))
      (node (ref "IC3") (pin "J4") (pinfunction "GND_J4") (pintype "power_in"))
      (node (ref "IC3") (pin "J5") (pinfunction "GND_J5") (pintype "power_in"))
      (node (ref "IC3") (pin "J6") (pinfunction "GND_J6") (pintype "power_in"))
      (node (ref "IC3") (pin "K3") (pinfunction "GND_K3") (pintype "power_in"))
      (node (ref "IC3") (pin "K4") (pinfunction "GND_K4") (pintype "power_in"))
      (node (ref "IC3") (pin "K5") (pinfunction "GND_K5") (pintype "power_in"))
      (node (ref "IC3") (pin "K6") (pinfunction "GND_K6") (pintype "power_in"))
      (node (ref "IC3") (pin "L3") (pinfunction "GND_L3") (pintype "power_in"))
      (node (ref "IC3") (pin "L4") (pinfunction "GND_L4") (pintype "power_in"))
      (node (ref "IC8") (pin "B5") (pinfunction "GND_B5") (pintype "power_in"))
      (node (ref "IC8") (pin "C1") (pinfunction "GND_C1") (pintype "power_in"))
      (node (ref "IC8") (pin "C2") (pinfunction "GND_C2") (pintype "power_in"))
      (node (ref "IC8") (pin "C5") (pinfunction "SYNC/MODE_C5") (pintype "input"))
      (node (ref "IC8") (pin "D5") (pinfunction "GND_D5") (pintype "power_in"))
      (node (ref "R108") (pin "1") (pinfunction "1_1") (pintype "passive"))
      (node (ref "R145") (pin "1") (pinfunction "1_1") (pintype "passive"))
      (node (ref "R181") (pin "1") (pinfunction "1_1") (pintype "passive"))
      (node (ref "R234") (pin "1") (pinfunction "1_1") (pintype "passive"))
      (node (ref "R237") (pin "1") (pinfunction "1_1") (pintype "passive"))
      (node (ref "R24") (pin "1") (pinfunction "1_1") (pintype "passive"))
      (node (ref "R56") (pin "1") (pinfunction "1_1") (pintype "passive"))
      (node (ref "R70") (pin "1") (pinfunction "1_1") (pintype "passive"))
      (node (ref "T8") (pin "2") (pinfunction "E_2") (pintype "passive"))
    )
    (net (code "3") (name "N13V0") (class "Default")
      (node (ref "C153") (pin "2") (pinfunction "2_2") (pintype "passive"))
      (node (ref "C156") (pin "2") (pinfunction "2_2") (pintype "passive"))
      (node (ref "L8") (pin "2") (pinfunction "2_2") (pintype "passive"))
    )
    (net (code "4") (name "N13V0S") (class "Default")
      (node (ref "C146") (pin "2") (pinfunction "2_2") (pintype "passive"))
      (node (ref "C147") (pin "2") (pinfunction "2_2") (pintype "passive"))
      (node (ref "C148") (pin "2") (pinfunction "2_2") (pintype "passive"))
      (node (ref "IC3") (pin "C2") (pinfunction "VOUT1N_C2") (pintype "power_in"))
      (node (ref "IC3") (pin "D1") (pinfunction "VOUT1N_D1") (pintype "power_in"))
      (node (ref "IC3") (pin "D2") (pinfunction "VOUT1N_D2") (pintype "power_in"))
      (node (ref "IC3") (pin "E1") (pinfunction "VOUT1N_E1") (pintype "power_in"))
      (node (ref "IC3") (pin "E2") (pinfunction "VOUT1N_E2") (pintype "power_in"))
      (node (ref "L7") (pin "1") (pinfunction "1_1") (pintype "passive"))
      (node (ref "R104") (pin "2") (pinfunction "2_2") (pintype "passive"))
    )
    (net (code "5") (name "N13V0_FLT") (class "Default")
      (node (ref "C150") (pin "2") (pinfunction "2_2") (pintype "passive"))
      (node (ref "C151") (pin "2") (pinfunction "2_2") (pintype "passive"))
      (node (ref "L7") (pin "2") (pinfunction "2_2") (pintype "passive"))
      (node (ref "L8") (pin "1") (pinfunction "1_1") (pintype "passive"))
    )
    (net (code "6") (name "Net-(D4-A)") (class "Default")
      (node (ref "C134") (pin "2") (pinfunction "2_2") (pintype "passive"))
      (node (ref "D4") (pin "2") (pinfunction "A_2") (pintype "passive"))
      (node (ref "IC8") (pin "B2") (pinfunction "RUN2_B2") (pintype "input"))
      (node (ref "R28") (pin "2") (pinfunction "2_2") (pintype "passive"))
    )
    (net (code "7") (name "Net-(IC3-CLKOUT1)") (class "Default")
      (node (ref "IC3") (pin "E6") (pinfunction "CLKOUT1_E6") (pintype "output"))
      (node (ref "R151") (pin "2") (pinfunction "2_2") (pintype "passive"))
    )
    (net (code "8") (name "Net-(IC3-FBX1)") (class "Default")
      (node (ref "IC3") (pin "C1") (pinfunction "FBX1_C1") (pintype "output"))
      (node (ref "R104") (pin "1") (pinfunction "1_1") (pintype "passive"))
    )
    (net (code "9") (name "Net-(IC3-FXB2)") (class "Default")
      (node (ref "IC3") (pin "J1") (pinfunction "FXB2_J1") (pintype "output"))
      (node (ref "R8") (pin "1") (pinfunction "1_1") (pintype "passive"))
    )
    (net (code "10") (name "Net-(IC3-RT1)") (class "Default")
      (node (ref "IC3") (pin "E7") (pinfunction "RT1_E7") (pintype "input"))
      (node (ref "R24") (pin "2") (pinfunction "2_2") (pintype "passive"))
    )
    (net (code "11") (name "Net-(IC3-RT2)") (class "Default")
      (node (ref "IC3") (pin "G7") (pinfunction "RT2_G7") (pintype "input"))
      (node (ref "R145") (pin "2") (pinfunction "2_2") (pintype "passive"))
    )
    (net (code "12") (name "Net-(IC3-RUN1)") (class "Default")
      (node (ref "IC3") (pin "B7") (pinfunction "RUN1_B7") (pintype "input"))
      (node (ref "R17") (pin "2") (pinfunction "2_2") (pintype "passive"))
    )
    (net (code "13") (name "Net-(IC3-RUN2)") (class "Default")
      (node (ref "IC3") (pin "K7") (pinfunction "RUN2_K7") (pintype "input"))
      (node (ref "R109") (pin "2") (pinfunction "2_2") (pintype "passive"))
    )
    (net (code "14") (name "Net-(IC3-SS1)") (class "Default")
      (node (ref "C102") (pin "1") (pinfunction "1_1") (pintype "passive"))
      (node (ref "IC3") (pin "C7") (pinfunction "SS1_C7") (pintype "passive"))
    )
    (net (code "15") (name "Net-(IC3-SS2)") (class "Default")
      (node (ref "C145") (pin "1") (pinfunction "1_1") (pintype "passive"))
      (node (ref "IC3") (pin "J7") (pinfunction "SS2_J7") (pintype "passive"))
    )
    (net (code "16") (name "Net-(IC3-SYNC2)") (class "Default")
      (node (ref "IC3") (pin "H7") (pinfunction "SYNC2_H7") (pintype "input"))
      (node (ref "R151") (pin "1") (pinfunction "1_1") (pintype "passive"))
    )
    (net (code "17") (name "Net-(IC8-FB1)") (class "Default")
      (node (ref "IC8") (pin "E4") (pinfunction "FB1_E4") (pintype "input"))
      (node (ref "R70") (pin "2") (pinfunction "2_2") (pintype "passive"))
    )
    (net (code "18") (name "Net-(IC8-FB2)") (class "Default")
      (node (ref "IC8") (pin "A4") (pinfunction "FB2_A4") (pintype "input"))
      (node (ref "R56") (pin "2") (pinfunction "2_2") (pintype "passive"))
    )
    (net (code "19") (name "Net-(IC8-FREQ)") (class "Default")
      (node (ref "IC8") (pin "C4") (pinfunction "FREQ_C4") (pintype "input"))
      (node (ref "R108") (pin "2") (pinfunction "2_2") (pintype "passive"))
    )
    (net (code "20") (name "Net-(IC8-TRACK{slash}SS1)") (class "Default")
      (node (ref "C110") (pin "1") (pinfunction "1_1") (pintype "passive"))
      (node (ref "IC8") (pin "E3") (pinfunction "TRACK/SS1_E3") (pintype "input"))
    )
    (net (code "21") (name "Net-(IC8-TRACK{slash}SS2)") (class "Default")
      (node (ref "C133") (pin "1") (pinfunction "1_1") (pintype "passive"))
      (node (ref "IC8") (pin "A3") (pinfunction "TRACK/SS2_A3") (pintype "input"))
    )
    (net (code "22") (name "Net-(IC18-FB1)") (class "Default")
      (node (ref "IC18") (pin "E4") (pinfunction "FB1_E4") (pintype "input"))
      (node (ref "R234") (pin "2") (pinfunction "2_2") (pintype "passive"))
    )
    (net (code "23") (name "Net-(IC18-FB2)") (class "Default")
      (node (ref "IC18") (pin "A4") (pinfunction "FB2_A4") (pintype "input"))
      (node (ref "R181") (pin "2") (pinfunction "2_2") (pintype "passive"))
    )
    (net (code "24") (name "Net-(IC18-FREQ)") (class "Default")
      (node (ref "IC18") (pin "C4") (pinfunction "FREQ_C4") (pintype "input"))
      (node (ref "R237") (pin "2") (pinfunction "2_2") (pintype "passive"))
    )
    (net (code "25") (name "Net-(IC18-RUN2)") (class "Default")
      (node (ref "C169") (pin "2") (pinfunction "2_2") (pintype "passive"))
      (node (ref "IC18") (pin "B2") (pinfunction "RUN2_B2") (pintype "input"))
      (node (ref "R162") (pin "2") (pinfunction "2_2") (pintype "passive"))
    )
    (net (code "26") (name "Net-(IC18-TRACK{slash}SS1)") (class "Default")
      (node (ref "C163") (pin "1") (pinfunction "1_1") (pintype "passive"))
      (node (ref "IC18") (pin "E3") (pinfunction "TRACK/SS1_E3") (pintype "input"))
    )
    (net (code "27") (name "Net-(IC18-TRACK{slash}SS2)") (class "Default")
      (node (ref "C168") (pin "1") (pinfunction "1_1") (pintype "passive"))
      (node (ref "IC18") (pin "A3") (pinfunction "TRACK/SS2_A3") (pintype "input"))
    )
    (net (code "28") (name "Net-(T8-B)") (class "Default")
      (node (ref "C135") (pin "2") (pinfunction "2_2") (pintype "passive"))
      (node (ref "R82") (pin "2") (pinfunction "2_2") (pintype "passive"))
      (node (ref "T8") (pin "1") (pinfunction "B_1") (pintype "passive"))
    )
    (net (code "29") (name "Net-(T8-C)") (class "Default")
      (node (ref "R19") (pin "1") (pinfunction "1_1") (pintype "passive"))
      (node (ref "T7") (pin "3") (pinfunction "S_3") (pintype "passive"))
      (node (ref "T8") (pin "3") (pinfunction "C_3") (pintype "passive"))
    )
    (net (code "30") (name "P1V2") (class "Default")
      (node (ref "C160") (pin "2") (pinfunction "2_2") (pintype "passive"))
      (node (ref "C161") (pin "2") (pinfunction "2_2") (pintype "passive"))
      (node (ref "C162") (pin "2") (pinfunction "2_2") (pintype "passive"))
      (node (ref "IC18") (pin "D1") (pinfunction "VOUT1_D1") (pintype "power_in"))
      (node (ref "IC18") (pin "E1") (pinfunction "VOUT1_E1") (pintype "power_in"))
      (node (ref "R82") (pin "1") (pinfunction "1_1") (pintype "passive"))
    )
    (net (code "31") (name "P2V5") (class "Default")
      (node (ref "C164") (pin "2") (pinfunction "2_2") (pintype "passive"))
      (node (ref "C165") (pin "2") (pinfunction "2_2") (pintype "passive"))
      (node (ref "C166") (pin "2") (pinfunction "2_2") (pintype "passive"))
      (node (ref "IC18") (pin "A1") (pinfunction "VOUT2_A1") (pintype "power_in"))
      (node (ref "IC18") (pin "B1") (pinfunction "VOUT2_B1") (pintype "power_in"))
    )
    (net (code "32") (name "P3V3") (class "Default")
      (node (ref "C121") (pin "2") (pinfunction "2_2") (pintype "passive"))
      (node (ref "C123") (pin "2") (pinfunction "2_2") (pintype "passive"))
      (node (ref "R162") (pin "1") (pinfunction "1_1") (pintype "passive"))
      (node (ref "T7") (pin "1") (pinfunction "D_1") (pintype "passive"))
      (node (ref "T7") (pin "2") (pinfunction "D_2") (pintype "passive"))
      (node (ref "T7") (pin "5") (pinfunction "D_5") (pintype "passive"))
      (node (ref "T7") (pin "6") (pinfunction "D_6") (pintype "passive"))
    )
    (net (code "33") (name "P3V3_buck") (class "Default")
      (node (ref "C111") (pin "2") (pinfunction "2_2") (pintype "passive"))
      (node (ref "C114") (pin "2") (pinfunction "2_2") (pintype "passive"))
      (node (ref "C117") (pin "2") (pinfunction "2_2") (pintype "passive"))
      (node (ref "C158") (pin "2") (pinfunction "2_2") (pintype "passive"))
      (node (ref "C159") (pin "2") (pinfunction "2_2") (pintype "passive"))
      (node (ref "IC18") (pin "A2") (pinfunction "VIN2_A2") (pintype "input"))
      (node (ref "IC18") (pin "B3") (pinfunction "VIN2_B3") (pintype "input"))
      (node (ref "IC18") (pin "D2") (pinfunction "RUN1_D2") (pintype "input"))
      (node (ref "IC18") (pin "D3") (pinfunction "VIN1_D3") (pintype "input"))
      (node (ref "IC18") (pin "E2") (pinfunction "VIN1_E2") (pintype "input"))
      (node (ref "IC8") (pin "A1") (pinfunction "VOUT2_A1") (pintype "power_in"))
      (node (ref "IC8") (pin "B1") (pinfunction "VOUT2_B1") (pintype "power_in"))
      (node (ref "R19") (pin "2") (pinfunction "2_2") (pintype "passive"))
      (node (ref "T7") (pin "4") (pinfunction "S_4") (pintype "passive"))
    )
    (net (code "34") (name "P6V0") (class "Default")
      (node (ref "C40") (pin "2") (pinfunction "2_2") (pintype "passive"))
      (node (ref "C42") (pin "2") (pinfunction "2_2") (pintype "passive"))
      (node (ref "C44") (pin "2") (pinfunction "2_2") (pintype "passive"))
      (node (ref "IC8") (pin "D1") (pinfunction "VOUT1_D1") (pintype "power_in"))
      (node (ref "IC8") (pin "E1") (pinfunction "VOUT1_E1") (pintype "power_in"))
      (node (ref "L1") (pin "1") (pinfunction "1_1") (pintype "passive"))
    )
    (net (code "35") (name "P6V0A") (class "Default")
      (node (ref "C58") (pin "2") (pinfunction "2_2") (pintype "passive"))
      (node (ref "D4") (pin "1") (pinfunction "C_1") (pintype "passive"))
      (node (ref "L1") (pin "2") (pinfunction "2_2") (pintype "passive"))
      (node (ref "R28") (pin "1") (pinfunction "1_1") (pintype "passive"))
    )
    (net (code "36") (name "P12V0F") (class "Default")
      (node (ref "C137") (pin "2") (pinfunction "2_2") (pintype "passive"))
      (node (ref "C144") (pin "2") (pinfunction "2_2") (pintype "passive"))
      (node (ref "C36") (pin "2") (pinfunction "2_2") (pintype "passive"))
      (node (ref "C39") (pin "2") (pinfunction "2_2") (pintype "passive"))
      (node (ref "C60") (pin "2") (pinfunction "2_2") (pintype "passive"))
      (node (ref "C63") (pin "2") (pinfunction "2_2") (pintype "passive"))
      (node (ref "IC3") (pin "A5") (pinfunction "VIN1_A5") (pintype "input"))
      (node (ref "IC3") (pin "A6") (pinfunction "VIN1_A6") (pintype "input"))
      (node (ref "IC3") (pin "A7") (pinfunction "VIN1_A7") (pintype "input"))
      (node (ref "IC3") (pin "L5") (pinfunction "VIN2_L5") (pintype "input"))
      (node (ref "IC3") (pin "L6") (pinfunction "VIN2_L6") (pintype "input"))
      (node (ref "IC3") (pin "L7") (pinfunction "VIN2_L7") (pintype "input"))
      (node (ref "IC8") (pin "A2") (pinfunction "VIN1_A2") (pintype "input"))
      (node (ref "IC8") (pin "B3") (pinfunction "VIN1_B3") (pintype "input"))
      (node (ref "IC8") (pin "D3") (pinfunction "VIN2_D3") (pintype "input"))
      (node (ref "IC8") (pin "E2") (pinfunction "VIN2_E2") (pintype "input"))
      (node (ref "R109") (pin "1") (pinfunction "1_1") (pintype "passive"))
      (node (ref "R17") (pin "1") (pinfunction "1_1") (pintype "passive"))
    )
    (net (code "37") (name "P13V0") (class "Default")
      (node (ref "C82") (pin "2") (pinfunction "2_2") (pintype "passive"))
      (node (ref "C93") (pin "2") (pinfunction "2_2") (pintype "passive"))
      (node (ref "L4") (pin "2") (pinfunction "2_2") (pintype "passive"))
    )
    (net (code "38") (name "P13V0S") (class "Default")
      (node (ref "C64") (pin "2") (pinfunction "2_2") (pintype "passive"))
      (node (ref "C69") (pin "2") (pinfunction "2_2") (pintype "passive"))
      (node (ref "C77") (pin "2") (pinfunction "2_2") (pintype "passive"))
      (node (ref "IC3") (pin "K1") (pinfunction "VOUT2P_K1") (pintype "power_in"))
      (node (ref "IC3") (pin "K2") (pinfunction "VOUT2P_K2") (pintype "power_in"))
      (node (ref "IC3") (pin "L1") (pinfunction "VOUT2P_L1") (pintype "power_in"))
      (node (ref "IC3") (pin "L2") (pinfunction "VOUT2P_L2") (pintype "power_in"))
      (node (ref "L3") (pin "1") (pinfunction "1_1") (pintype "passive"))
      (node (ref "R8") (pin "2") (pinfunction "2_2") (pintype "passive"))
    )
    (net (code "39") (name "P13V0_FLT") (class "Default")
      (node (ref "C28") (pin "1") (pinfunction "1_1") (pintype "passive"))
      (node (ref "C81") (pin "2") (pinfunction "2_2") (pintype "passive"))
      (node (ref "L3") (pin "2") (pinfunction "2_2") (pintype "passive"))
      (node (ref "L4") (pin "1") (pinfunction "1_1") (pintype "passive"))
    )
    (net (code "40") (name "unconnected-(IC3-CLKOUT2-PadG6)") (class "Default")
      (node (ref "IC3") (pin "G6") (pinfunction "CLKOUT2_G6") (pintype "output+no_connect"))
    )
    (net (code "41") (name "unconnected-(IC3-PG1-PadD6)") (class "Default")
      (node (ref "IC3") (pin "D6") (pinfunction "PG1_D6") (pintype "output+no_connect"))
    )
    (net (code "42") (name "unconnected-(IC3-PG2-PadH6)") (class "Default")
      (node (ref "IC3") (pin "H6") (pinfunction "PG2_H6") (pintype "output+no_connect"))
    )
    (net (code "43") (name "unconnected-(IC3-SHARE1-PadF3)") (class "Default")
      (node (ref "IC3") (pin "F3") (pinfunction "SHARE1_F3") (pintype "input+no_connect"))
    )
    (net (code "44") (name "unconnected-(IC3-SHARE2-PadF4)") (class "Default")
      (node (ref "IC3") (pin "F4") (pinfunction "SHARE2_F4") (pintype "input+no_connect"))
    )
    (net (code "45") (name "unconnected-(IC3-SYNC1-PadD7)") (class "Default")
      (node (ref "IC3") (pin "D7") (pinfunction "SYNC1_D7") (pintype "input+no_connect"))
    )
    (net (code "46") (name "unconnected-(IC8-COMP1-PadE5)") (class "Default")
      (node (ref "IC8") (pin "E5") (pinfunction "COMP1_E5") (pintype "input+no_connect"))
    )
    (net (code "47") (name "unconnected-(IC8-COMP2-PadA5)") (class "Default")
      (node (ref "IC8") (pin "A5") (pinfunction "COMP2_A5") (pintype "input+no_connect"))
    )
    (net (code "48") (name "unconnected-(IC8-INTVCC-PadC3)") (class "Default")
      (node (ref "IC8") (pin "C3") (pinfunction "INTVCC_C3") (pintype "power_in+no_connect"))
    )
    (net (code "49") (name "unconnected-(IC8-PGOOD1-PadD4)") (class "Default")
      (node (ref "IC8") (pin "D4") (pinfunction "PGOOD1_D4") (pintype "open_collector+no_connect"))
    )
    (net (code "50") (name "unconnected-(IC8-PGOOD2-PadB4)") (class "Default")
      (node (ref "IC8") (pin "B4") (pinfunction "PGOOD2_B4") (pintype "open_collector+no_connect"))
    )
    (net (code "51") (name "unconnected-(IC18-COMP1-PadE5)") (class "Default")
      (node (ref "IC18") (pin "E5") (pinfunction "COMP1_E5") (pintype "input+no_connect"))
    )
    (net (code "52") (name "unconnected-(IC18-COMP2-PadA5)") (class "Default")
      (node (ref "IC18") (pin "A5") (pinfunction "COMP2_A5") (pintype "input+no_connect"))
    )
    (net (code "53") (name "unconnected-(IC18-INTVCC-PadC3)") (class "Default")
      (node (ref "IC18") (pin "C3") (pinfunction "INTVCC_C3") (pintype "power_in+no_connect"))
    )
    (net (code "54") (name "unconnected-(IC18-PGOOD1-PadD4)") (class "Default")
      (node (ref "IC18") (pin "D4") (pinfunction "PGOOD1_D4") (pintype "open_collector+no_connect"))
    )
    (net (code "55") (name "unconnected-(IC18-PGOOD2-PadB4)") (class "Default")
      (node (ref "IC18") (pin "B4") (pinfunction "PGOOD2_B4") (pintype "open_collector+no_connect"))
    )
  )
)
